# flatkeys_sch.net
KiCad netlist of a schematic drawn in EasyEDA
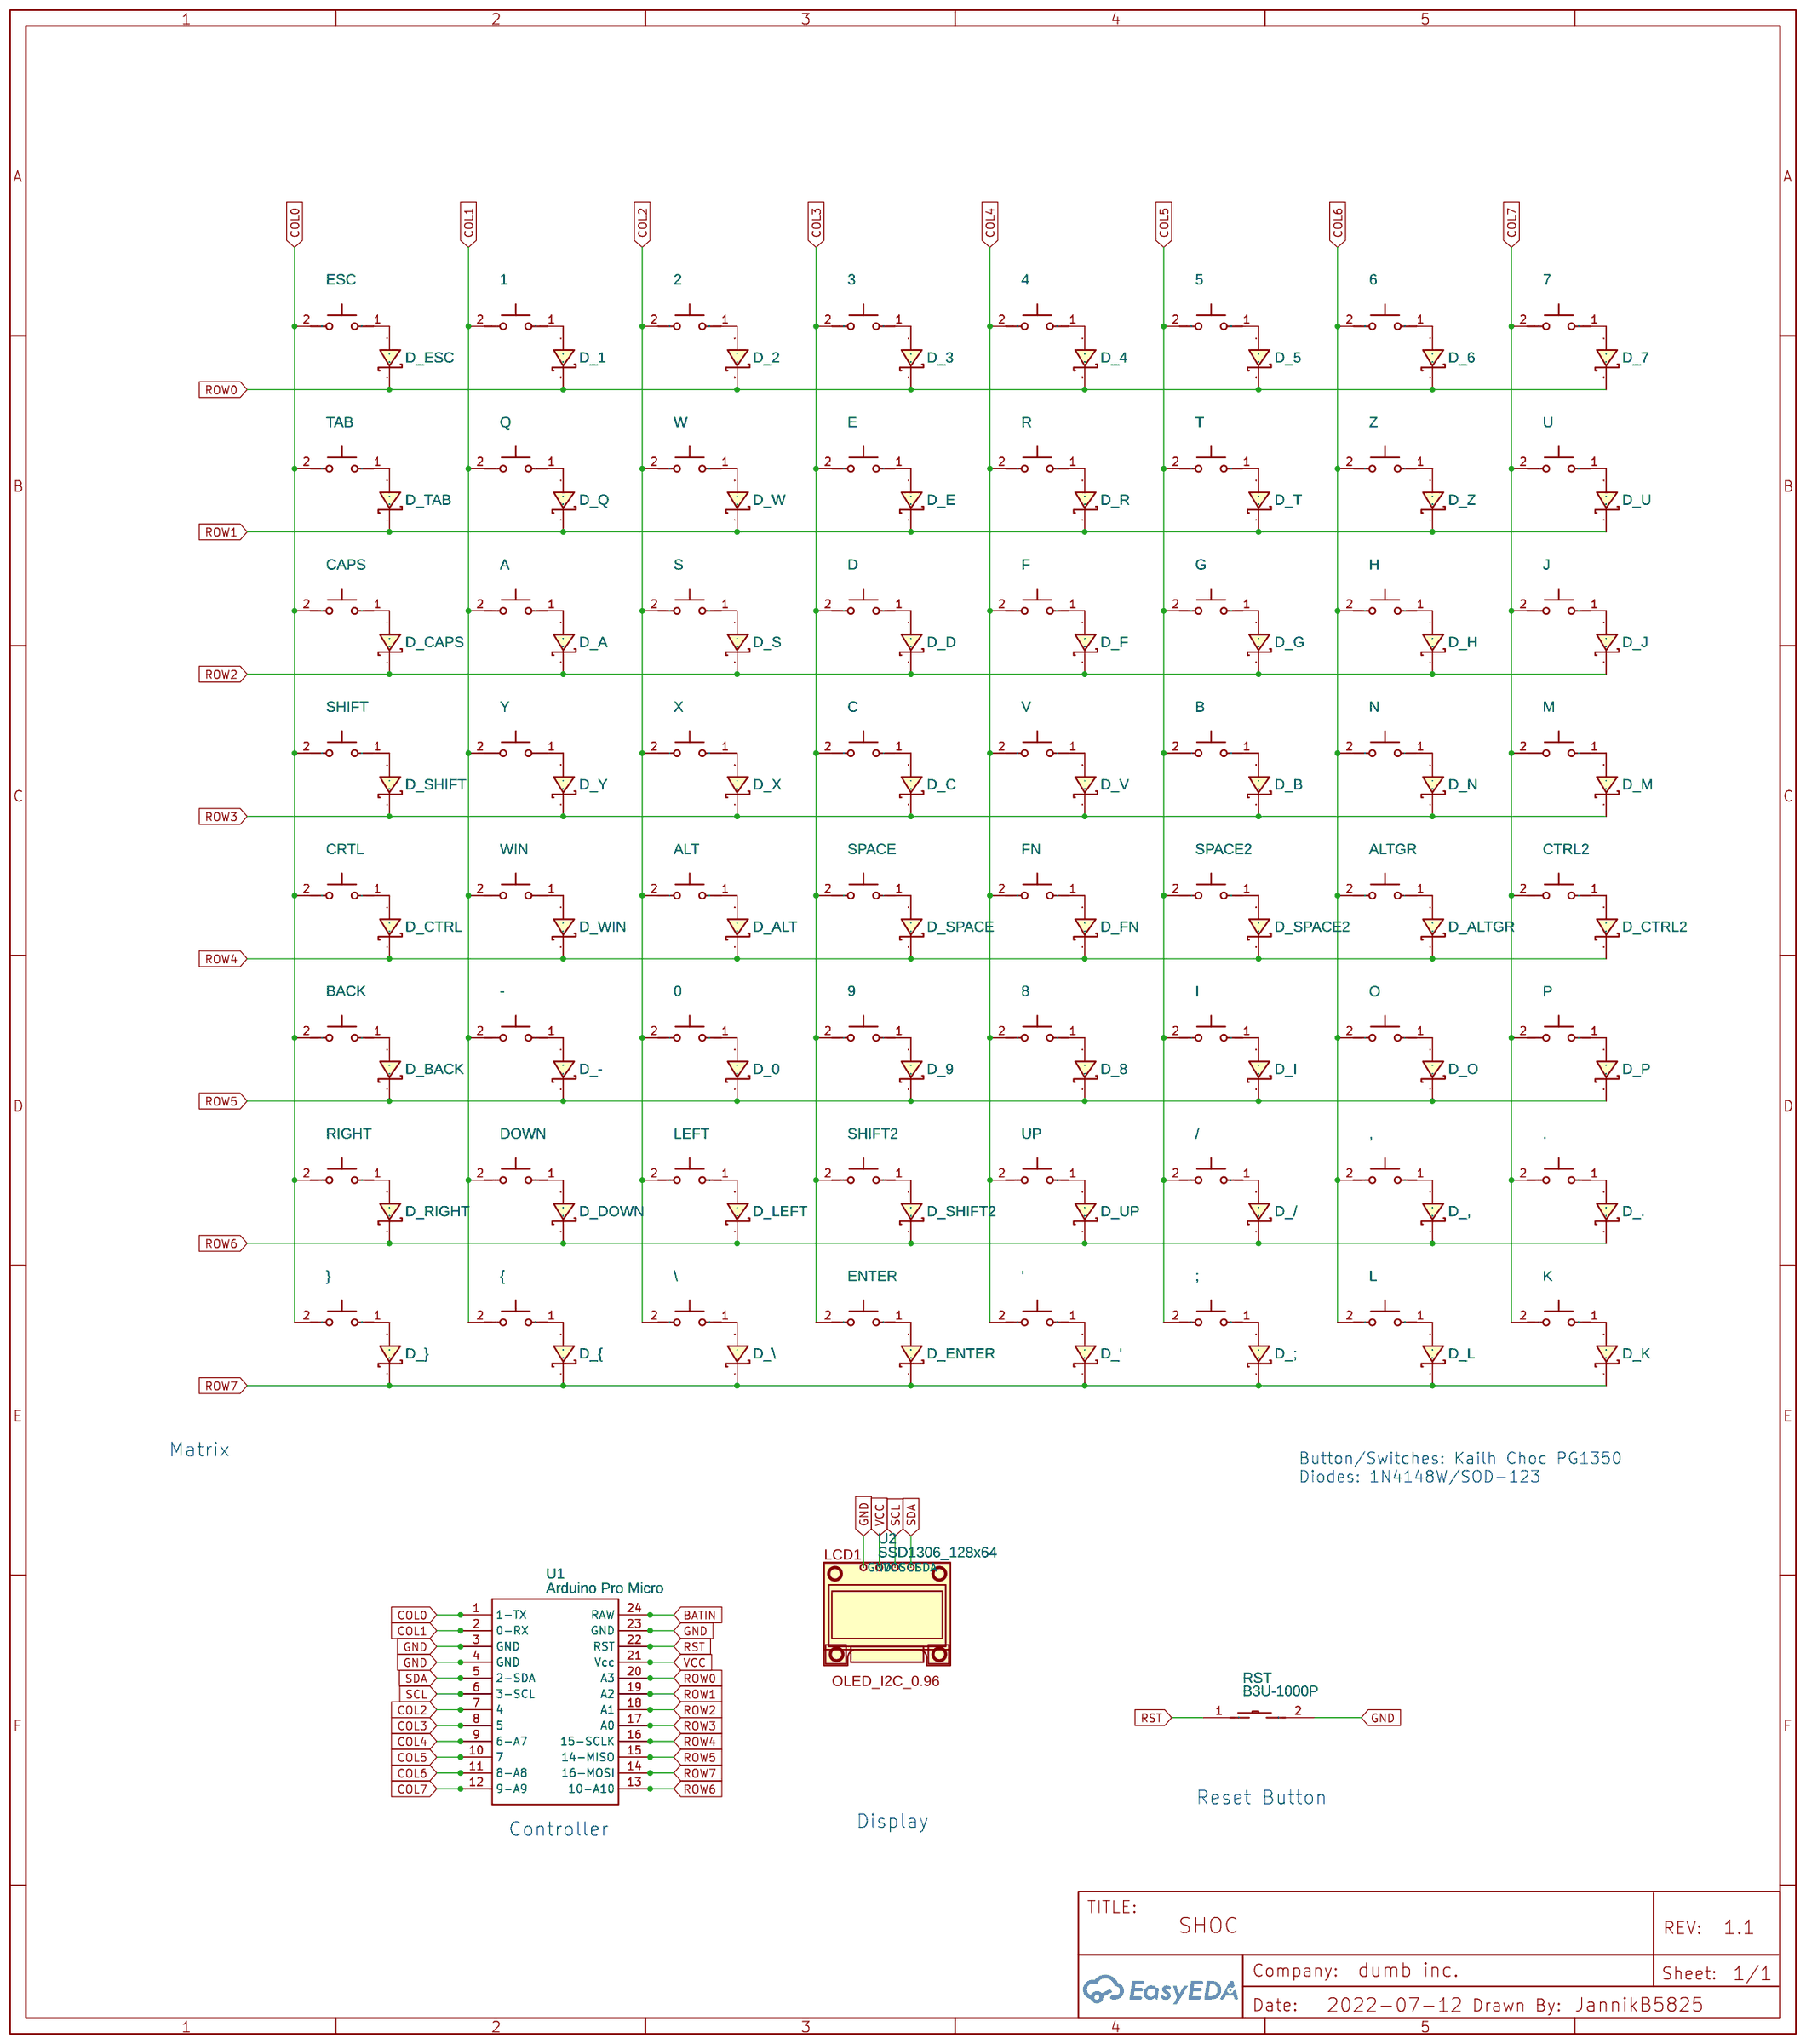
[diagram p0: schematic sheet]

(export (version "E")
  (design (tool "Eeschema 10.0.6"))
  (components
    (comp (ref "'")
      (value "PG1350")
      (fields (field (name "Manufacturer Part") "CPG135001D02") (field (name "Manufacturer") "Kailh"))
      (libsource (lib "") (part "PG1350_43"))
    )
    (comp (ref ",")
      (value "PG1350")
      (fields (field (name "Manufacturer Part") "CPG135001D02") (field (name "Manufacturer") "Kailh"))
      (libsource (lib "") (part "PG1350_28"))
    )
    (comp (ref "-")
      (value "PG1350")
      (fields (field (name "Manufacturer Part") "CPG135001D02") (field (name "Manufacturer") "Kailh"))
      (libsource (lib "") (part "PG1350_25"))
    )
    (comp (ref ".")
      (value "PG1350")
      (fields (field (name "Manufacturer Part") "CPG135001D02") (field (name "Manufacturer") "Kailh"))
      (libsource (lib "") (part "PG1350_46"))
    )
    (comp (ref "/")
      (value "PG1350")
      (fields (field (name "Manufacturer Part") "CPG135001D02") (field (name "Manufacturer") "Kailh"))
      (libsource (lib "") (part "PG1350_21"))
    )
    (comp (ref "0")
      (value "PG1350")
      (fields (field (name "Manufacturer Part") "CPG135001D02") (field (name "Manufacturer") "Kailh"))
      (libsource (lib "") (part "PG1350_2"))
    )
    (comp (ref "1")
      (value "PG1350")
      (fields (field (name "Manufacturer Part") "CPG135001D02") (field (name "Manufacturer") "Kailh"))
      (libsource (lib "") (part "PG1350_2"))
    )
    (comp (ref "2")
      (value "PG1350")
      (fields (field (name "Manufacturer Part") "CPG135001D02") (field (name "Manufacturer") "Kailh"))
      (libsource (lib "") (part "PG1350_2"))
    )
    (comp (ref "3")
      (value "PG1350")
      (fields (field (name "Manufacturer Part") "CPG135001D02") (field (name "Manufacturer") "Kailh"))
      (libsource (lib "") (part "PG1350_2"))
    )
    (comp (ref "4")
      (value "PG1350")
      (fields (field (name "Manufacturer Part") "CPG135001D02") (field (name "Manufacturer") "Kailh"))
      (libsource (lib "") (part "PG1350_2"))
    )
    (comp (ref "5")
      (value "PG1350")
      (fields (field (name "Manufacturer Part") "CPG135001D02") (field (name "Manufacturer") "Kailh"))
      (libsource (lib "") (part "PG1350_2"))
    )
    (comp (ref "6")
      (value "PG1350")
      (fields (field (name "Manufacturer Part") "CPG135001D02") (field (name "Manufacturer") "Kailh"))
      (libsource (lib "") (part "PG1350_2"))
    )
    (comp (ref "7")
      (value "PG1350")
      (fields (field (name "Manufacturer Part") "CPG135001D02") (field (name "Manufacturer") "Kailh"))
      (libsource (lib "") (part "PG1350_2"))
    )
    (comp (ref "8")
      (value "PG1350")
      (fields (field (name "Manufacturer Part") "CPG135001D02") (field (name "Manufacturer") "Kailh"))
      (libsource (lib "") (part "PG1350_2"))
    )
    (comp (ref "9")
      (value "PG1350")
      (fields (field (name "Manufacturer Part") "CPG135001D02") (field (name "Manufacturer") "Kailh"))
      (libsource (lib "") (part "PG1350_2"))
    )
    (comp (ref ";")
      (value "PG1350")
      (fields (field (name "Manufacturer Part") "CPG135001D02") (field (name "Manufacturer") "Kailh"))
      (libsource (lib "") (part "PG1350_11"))
    )
    (comp (ref "A")
      (value "PG1350")
      (fields (field (name "Manufacturer Part") "?"))
      (libsource (lib "") (part "Unknown_205_-1510"))
    )
    (comp (ref "ALT")
      (value "PG1350")
      (fields (field (name "Manufacturer Part") "CPG135001D02") (field (name "Manufacturer") "Kailh"))
      (libsource (lib "") (part "PG1350_6"))
    )
    (comp (ref "ALTGR")
      (value "PG1350")
      (fields (field (name "Manufacturer Part") "CPG135001D02") (field (name "Manufacturer") "Kailh"))
      (libsource (lib "") (part "PG1350_37"))
    )
    (comp (ref "B")
      (value "PG1350")
      (fields (field (name "Manufacturer Part") "CPG135001D02") (field (name "Manufacturer") "Kailh"))
      (libsource (lib "") (part "PG1350_19"))
    )
    (comp (ref "BACK")
      (value "PG1350")
      (fields (field (name "Manufacturer Part") "CPG135001D02") (field (name "Manufacturer") "Kailh"))
      (libsource (lib "") (part "PG1350_3"))
    )
    (comp (ref "C")
      (value "PG1350")
      (fields (field (name "Manufacturer Part") "CPG135001D02") (field (name "Manufacturer") "Kailh"))
      (libsource (lib "") (part "PG1350_31"))
    )
    (comp (ref "CAPS")
      (value "PG1350")
      (fields (field (name "Manufacturer Part") "CPG135001D02") (field (name "Manufacturer") "Kailh"))
      (libsource (lib "") (part "PG1350_52"))
    )
    (comp (ref "CRTL")
      (value "PG1350")
      (fields (field (name "Manufacturer Part") "CPG135001D02") (field (name "Manufacturer") "Kailh"))
      (libsource (lib "") (part "PG1350_12"))
    )
    (comp (ref "CTRL2")
      (value "PG1350")
      (fields (field (name "Manufacturer Part") "CPG135001D02") (field (name "Manufacturer") "Kailh"))
      (libsource (lib "") (part "PG1350_4"))
    )
    (comp (ref "D")
      (value "PG1350")
      (fields (field (name "Manufacturer Part") "CPG135001D02") (field (name "Manufacturer") "Kailh"))
      (libsource (lib "") (part "PG1350_7"))
    )
    (comp (ref "DOWN")
      (value "PG1350")
      (fields (field (name "Manufacturer Part") "CPG135001D02") (field (name "Manufacturer") "Kailh"))
      (libsource (lib "") (part "PG1350"))
    )
    (comp (ref "D_'")
      (value "MBR2H200SFT3G")
      (fields (field (name "Manufacturer") "ON Semiconductor"))
      (libsource (lib "") (part "MBR2H200SFT3G_10"))
    )
    (comp (ref "D_,")
      (value "MBR2H200SFT3G")
      (fields (field (name "Manufacturer") "ON Semiconductor"))
      (libsource (lib "") (part "MBR2H200SFT3G_22"))
    )
    (comp (ref "D_-")
      (value "MBR2H200SFT3G")
      (fields (field (name "Manufacturer") "ON Semiconductor"))
      (libsource (lib "") (part "MBR2H200SFT3G_40"))
    )
    (comp (ref "D_.")
      (value "MBR2H200SFT3G")
      (fields (field (name "Manufacturer") "ON Semiconductor"))
      (libsource (lib "") (part "MBR2H200SFT3G_17"))
    )
    (comp (ref "D_/")
      (value "MBR2H200SFT3G")
      (fields (field (name "Manufacturer") "ON Semiconductor"))
      (libsource (lib "") (part "MBR2H200SFT3G_13"))
    )
    (comp (ref "D_0")
      (value "MBR2H200SFT3G")
      (fields (field (name "Manufacturer") "ON Semiconductor"))
      (libsource (lib "") (part "MBR2H200SFT3G_4"))
    )
    (comp (ref "D_1")
      (value "MBR2H200SFT3G")
      (fields (field (name "Manufacturer") "ON Semiconductor"))
      (libsource (lib "") (part "MBR2H200SFT3G_4"))
    )
    (comp (ref "D_2")
      (value "MBR2H200SFT3G")
      (fields (field (name "Manufacturer") "ON Semiconductor"))
      (libsource (lib "") (part "MBR2H200SFT3G_4"))
    )
    (comp (ref "D_3")
      (value "MBR2H200SFT3G")
      (fields (field (name "Manufacturer") "ON Semiconductor"))
      (libsource (lib "") (part "MBR2H200SFT3G_4"))
    )
    (comp (ref "D_4")
      (value "MBR2H200SFT3G")
      (fields (field (name "Manufacturer") "ON Semiconductor"))
      (libsource (lib "") (part "MBR2H200SFT3G_4"))
    )
    (comp (ref "D_5")
      (value "MBR2H200SFT3G")
      (fields (field (name "Manufacturer") "ON Semiconductor"))
      (libsource (lib "") (part "MBR2H200SFT3G_4"))
    )
    (comp (ref "D_6")
      (value "MBR2H200SFT3G")
      (fields (field (name "Manufacturer") "ON Semiconductor"))
      (libsource (lib "") (part "MBR2H200SFT3G_4"))
    )
    (comp (ref "D_7")
      (value "MBR2H200SFT3G")
      (fields (field (name "Manufacturer") "ON Semiconductor"))
      (libsource (lib "") (part "MBR2H200SFT3G_4"))
    )
    (comp (ref "D_8")
      (value "MBR2H200SFT3G")
      (fields (field (name "Manufacturer") "ON Semiconductor"))
      (libsource (lib "") (part "MBR2H200SFT3G_4"))
    )
    (comp (ref "D_9")
      (value "MBR2H200SFT3G")
      (fields (field (name "Manufacturer") "ON Semiconductor"))
      (libsource (lib "") (part "MBR2H200SFT3G_4"))
    )
    (comp (ref "D_;")
      (value "MBR2H200SFT3G")
      (fields (field (name "Manufacturer") "ON Semiconductor"))
      (libsource (lib "") (part "MBR2H200SFT3G_9"))
    )
    (comp (ref "D_A")
      (value "MBR2H200SFT3G")
      (fields (field (name "Manufacturer") "ON Semiconductor"))
      (libsource (lib "") (part "MBR2H200SFT3G_44"))
    )
    (comp (ref "D_ALT")
      (value "MBR2H200SFT3G")
      (fields (field (name "Manufacturer") "ON Semiconductor"))
      (libsource (lib "") (part "MBR2H200SFT3G_14"))
    )
    (comp (ref "D_ALTGR")
      (value "MBR2H200SFT3G")
      (fields (field (name "Manufacturer") "ON Semiconductor"))
      (libsource (lib "") (part "MBR2H200SFT3G_34"))
    )
    (comp (ref "D_B")
      (value "MBR2H200SFT3G")
      (fields (field (name "Manufacturer") "ON Semiconductor"))
      (libsource (lib "") (part "MBR2H200SFT3G_28"))
    )
    (comp (ref "D_BACK")
      (value "MBR2H200SFT3G")
      (fields (field (name "Manufacturer") "ON Semiconductor"))
      (libsource (lib "") (part "MBR2H200SFT3G_21"))
    )
    (comp (ref "D_C")
      (value "MBR2H200SFT3G")
      (fields (field (name "Manufacturer") "ON Semiconductor"))
      (libsource (lib "") (part "MBR2H200SFT3G_24"))
    )
    (comp (ref "D_CAPS")
      (value "MBR2H200SFT3G")
      (fields (field (name "Manufacturer") "ON Semiconductor"))
      (libsource (lib "") (part "MBR2H200SFT3G_43"))
    )
    (comp (ref "D_CTRL")
      (value "MBR2H200SFT3G")
      (fields (field (name "Manufacturer") "ON Semiconductor"))
      (libsource (lib "") (part "MBR2H200SFT3G"))
    )
    (comp (ref "D_CTRL2")
      (value "MBR2H200SFT3G")
      (fields (field (name "Manufacturer") "ON Semiconductor"))
      (libsource (lib "") (part "MBR2H200SFT3G"))
    )
    (comp (ref "D_D")
      (value "MBR2H200SFT3G")
      (fields (field (name "Manufacturer") "ON Semiconductor"))
      (libsource (lib "") (part "MBR2H200SFT3G_38"))
    )
    (comp (ref "D_DOWN")
      (value "MBR2H200SFT3G")
      (fields (field (name "Manufacturer") "ON Semiconductor"))
      (libsource (lib "") (part "MBR2H200SFT3G_25"))
    )
    (comp (ref "D_E")
      (value "MBR2H200SFT3G")
      (fields (field (name "Manufacturer") "ON Semiconductor"))
      (libsource (lib "") (part "MBR2H200SFT3G_41"))
    )
    (comp (ref "D_ENTER")
      (value "MBR2H200SFT3G")
      (fields (field (name "Manufacturer") "ON Semiconductor"))
      (libsource (lib "") (part "MBR2H200SFT3G_47"))
    )
    (comp (ref "D_ESC")
      (value "MBR2H200SFT3G")
      (fields (field (name "Manufacturer") "ON Semiconductor"))
      (libsource (lib "") (part "MBR2H200SFT3G_15"))
    )
    (comp (ref "D_F")
      (value "MBR2H200SFT3G")
      (fields (field (name "Manufacturer") "ON Semiconductor"))
      (libsource (lib "") (part "MBR2H200SFT3G_48"))
    )
    (comp (ref "D_FN")
      (value "MBR2H200SFT3G")
      (fields (field (name "Manufacturer") "ON Semiconductor"))
      (libsource (lib "") (part "MBR2H200SFT3G_32"))
    )
    (comp (ref "D_G")
      (value "MBR2H200SFT3G")
      (fields (field (name "Manufacturer") "ON Semiconductor"))
      (libsource (lib "") (part "MBR2H200SFT3G_6"))
    )
    (comp (ref "D_H")
      (value "MBR2H200SFT3G")
      (fields (field (name "Manufacturer") "ON Semiconductor"))
      (libsource (lib "") (part "MBR2H200SFT3G_39"))
    )
    (comp (ref "D_I")
      (value "MBR2H200SFT3G")
      (fields (field (name "Manufacturer") "ON Semiconductor"))
      (libsource (lib "") (part "MBR2H200SFT3G_49"))
    )
    (comp (ref "D_J")
      (value "MBR2H200SFT3G")
      (fields (field (name "Manufacturer") "ON Semiconductor"))
      (libsource (lib "") (part "MBR2H200SFT3G_8"))
    )
    (comp (ref "D_K")
      (value "MBR2H200SFT3G")
      (fields (field (name "Manufacturer") "ON Semiconductor"))
      (libsource (lib "") (part "MBR2H200SFT3G_26"))
    )
    (comp (ref "D_L")
      (value "MBR2H200SFT3G")
      (fields (field (name "Manufacturer") "ON Semiconductor"))
      (libsource (lib "") (part "MBR2H200SFT3G_31"))
    )
    (comp (ref "D_LEFT")
      (value "MBR2H200SFT3G")
      (fields (field (name "Manufacturer") "ON Semiconductor"))
      (libsource (lib "") (part "MBR2H200SFT3G_19"))
    )
    (comp (ref "D_M")
      (value "MBR2H200SFT3G")
      (fields (field (name "Manufacturer") "ON Semiconductor"))
      (libsource (lib "") (part "MBR2H200SFT3G_46"))
    )
    (comp (ref "D_N")
      (value "MBR2H200SFT3G")
      (fields (field (name "Manufacturer") "ON Semiconductor"))
      (libsource (lib "") (part "MBR2H200SFT3G_23"))
    )
    (comp (ref "D_O")
      (value "MBR2H200SFT3G")
      (fields (field (name "Manufacturer") "ON Semiconductor"))
      (libsource (lib "") (part "MBR2H200SFT3G_7"))
    )
    (comp (ref "D_P")
      (value "MBR2H200SFT3G")
      (fields (field (name "Manufacturer") "ON Semiconductor"))
      (libsource (lib "") (part "MBR2H200SFT3G_27"))
    )
    (comp (ref "D_Q")
      (value "MBR2H200SFT3G")
      (fields (field (name "Manufacturer") "ON Semiconductor"))
      (libsource (lib "") (part "MBR2H200SFT3G_11"))
    )
    (comp (ref "D_R")
      (value "MBR2H200SFT3G")
      (fields (field (name "Manufacturer") "ON Semiconductor"))
      (libsource (lib "") (part "MBR2H200SFT3G_51"))
    )
    (comp (ref "D_RIGHT")
      (value "MBR2H200SFT3G")
      (fields (field (name "Manufacturer") "ON Semiconductor"))
      (libsource (lib "") (part "MBR2H200SFT3G_29"))
    )
    (comp (ref "D_S")
      (value "MBR2H200SFT3G")
      (fields (field (name "Manufacturer") "ON Semiconductor"))
      (libsource (lib "") (part "MBR2H200SFT3G_30"))
    )
    (comp (ref "D_SHIFT")
      (value "MBR2H200SFT3G")
      (fields (field (name "Manufacturer") "ON Semiconductor"))
      (libsource (lib "") (part "MBR2H200SFT3G_1"))
    )
    (comp (ref "D_SHIFT2")
      (value "MBR2H200SFT3G")
      (fields (field (name "Manufacturer") "ON Semiconductor"))
      (libsource (lib "") (part "MBR2H200SFT3G_1"))
    )
    (comp (ref "D_SPACE")
      (value "MBR2H200SFT3G")
      (fields (field (name "Manufacturer") "ON Semiconductor"))
      (libsource (lib "") (part "MBR2H200SFT3G_12"))
    )
    (comp (ref "D_SPACE2")
      (value "MBR2H200SFT3G")
      (fields (field (name "Manufacturer") "ON Semiconductor"))
      (libsource (lib "") (part "MBR2H200SFT3G_12"))
    )
    (comp (ref "D_T")
      (value "MBR2H200SFT3G")
      (fields (field (name "Manufacturer") "ON Semiconductor"))
      (libsource (lib "") (part "MBR2H200SFT3G_35"))
    )
    (comp (ref "D_TAB")
      (value "MBR2H200SFT3G")
      (fields (field (name "Manufacturer") "ON Semiconductor"))
      (libsource (lib "") (part "MBR2H200SFT3G_20"))
    )
    (comp (ref "D_U")
      (value "MBR2H200SFT3G")
      (fields (field (name "Manufacturer") "ON Semiconductor"))
      (libsource (lib "") (part "MBR2H200SFT3G_33"))
    )
    (comp (ref "D_UP")
      (value "MBR2H200SFT3G")
      (fields (field (name "Manufacturer") "ON Semiconductor"))
      (libsource (lib "") (part "MBR2H200SFT3G_16"))
    )
    (comp (ref "D_V")
      (value "MBR2H200SFT3G")
      (fields (field (name "Manufacturer") "ON Semiconductor"))
      (libsource (lib "") (part "MBR2H200SFT3G_45"))
    )
    (comp (ref "D_W")
      (value "MBR2H200SFT3G")
      (fields (field (name "Manufacturer") "ON Semiconductor"))
      (libsource (lib "") (part "MBR2H200SFT3G_50"))
    )
    (comp (ref "D_WIN")
      (value "MBR2H200SFT3G")
      (fields (field (name "Manufacturer") "ON Semiconductor"))
      (libsource (lib "") (part "MBR2H200SFT3G_3"))
    )
    (comp (ref "D_X")
      (value "MBR2H200SFT3G")
      (fields (field (name "Manufacturer") "ON Semiconductor"))
      (libsource (lib "") (part "MBR2H200SFT3G_5"))
    )
    (comp (ref "D_Y")
      (value "MBR2H200SFT3G")
      (fields (field (name "Manufacturer") "ON Semiconductor"))
      (libsource (lib "") (part "MBR2H200SFT3G_37"))
    )
    (comp (ref "D_Z")
      (value "MBR2H200SFT3G")
      (fields (field (name "Manufacturer") "ON Semiconductor"))
      (libsource (lib "") (part "MBR2H200SFT3G_2"))
    )
    (comp (ref "D_\\")
      (value "MBR2H200SFT3G")
      (fields (field (name "Manufacturer") "ON Semiconductor"))
      (libsource (lib "") (part "MBR2H200SFT3G_42"))
    )
    (comp (ref "D_{")
      (value "MBR2H200SFT3G")
      (fields (field (name "Manufacturer") "ON Semiconductor"))
      (libsource (lib "") (part "MBR2H200SFT3G_36"))
    )
    (comp (ref "D_}")
      (value "MBR2H200SFT3G")
      (fields (field (name "Manufacturer") "ON Semiconductor"))
      (libsource (lib "") (part "MBR2H200SFT3G_18"))
    )
    (comp (ref "E")
      (value "PG1350")
      (fields (field (name "Manufacturer Part") "CPG135001D02") (field (name "Manufacturer") "Kailh"))
      (libsource (lib "") (part "PG1350_23"))
    )
    (comp (ref "ENTER")
      (value "PG1350")
      (fields (field (name "Manufacturer Part") "CPG135001D02") (field (name "Manufacturer") "Kailh"))
      (libsource (lib "") (part "PG1350_9"))
    )
    (comp (ref "ESC")
      (value "PG1350")
      (fields (field (name "Manufacturer Part") "CPG135001D02") (field (name "Manufacturer") "Kailh"))
      (libsource (lib "") (part "PG1350_26"))
    )
    (comp (ref "F")
      (value "PG1350")
      (fields (field (name "Manufacturer Part") "CPG135001D02") (field (name "Manufacturer") "Kailh"))
      (libsource (lib "") (part "PG1350_44"))
    )
    (comp (ref "FN")
      (value "PG1350")
      (fields (field (name "Manufacturer Part") "CPG135001D02") (field (name "Manufacturer") "Kailh"))
      (libsource (lib "") (part "PG1350_49"))
    )
    (comp (ref "G")
      (value "PG1350")
      (fields (field (name "Manufacturer Part") "CPG135001D02") (field (name "Manufacturer") "Kailh"))
      (libsource (lib "") (part "PG1350_45"))
    )
    (comp (ref "H")
      (value "PG1350")
      (fields (field (name "Manufacturer Part") "CPG135001D02") (field (name "Manufacturer") "Kailh"))
      (libsource (lib "") (part "PG1350_1"))
    )
    (comp (ref "I")
      (value "PG1350")
      (fields (field (name "Manufacturer Part") "CPG135001D02") (field (name "Manufacturer") "Kailh"))
      (libsource (lib "") (part "PG1350_47"))
    )
    (comp (ref "J")
      (value "PG1350")
      (fields (field (name "Manufacturer Part") "CPG135001D02") (field (name "Manufacturer") "Kailh"))
      (libsource (lib "") (part "PG1350_41"))
    )
    (comp (ref "K")
      (value "PG1350")
      (fields (field (name "Manufacturer Part") "CPG135001D02") (field (name "Manufacturer") "Kailh"))
      (libsource (lib "") (part "PG1350_32"))
    )
    (comp (ref "L")
      (value "PG1350")
      (fields (field (name "Manufacturer Part") "CPG135001D02") (field (name "Manufacturer") "Kailh"))
      (libsource (lib "") (part "PG1350_16"))
    )
    (comp (ref "LEFT")
      (value "PG1350")
      (fields (field (name "Manufacturer Part") "CPG135001D02") (field (name "Manufacturer") "Kailh"))
      (libsource (lib "") (part "PG1350_22"))
    )
    (comp (ref "M")
      (value "PG1350")
      (fields (field (name "Manufacturer Part") "CPG135001D02") (field (name "Manufacturer") "Kailh"))
      (libsource (lib "") (part "PG1350_30"))
    )
    (comp (ref "N")
      (value "PG1350")
      (fields (field (name "Manufacturer Part") "CPG135001D02") (field (name "Manufacturer") "Kailh"))
      (libsource (lib "") (part "PG1350_14"))
    )
    (comp (ref "O")
      (value "PG1350")
      (fields (field (name "Manufacturer Part") "CPG135001D02") (field (name "Manufacturer") "Kailh"))
      (libsource (lib "") (part "PG1350_17"))
    )
    (comp (ref "P")
      (value "PG1350")
      (fields (field (name "Manufacturer Part") "CPG135001D02") (field (name "Manufacturer") "Kailh"))
      (libsource (lib "") (part "PG1350_8"))
    )
    (comp (ref "Q")
      (value "PG1350")
      (fields (field (name "Manufacturer Part") "CPG135001D02") (field (name "Manufacturer") "Kailh"))
      (libsource (lib "") (part "PG1350_40"))
    )
    (comp (ref "R")
      (value "PG1350")
      (fields (field (name "Manufacturer Part") "CPG135001D02") (field (name "Manufacturer") "Kailh"))
      (libsource (lib "") (part "PG1350_20"))
    )
    (comp (ref "RIGHT")
      (value "PG1350")
      (fields (field (name "Manufacturer Part") "CPG135001D02") (field (name "Manufacturer") "Kailh"))
      (libsource (lib "") (part "PG1350_42"))
    )
    (comp (ref "RST")
      (value "B3U-1000P")
      (fields (field (name "Manufacturer") "Omron Electronics"))
      (libsource (lib "") (part "B3U-1000P"))
    )
    (comp (ref "S")
      (value "PG1350")
      (fields (field (name "Manufacturer Part") "CPG135001D02") (field (name "Manufacturer") "Kailh"))
      (libsource (lib "") (part "PG1350_34"))
    )
    (comp (ref "SHIFT")
      (value "PG1350")
      (fields (field (name "Manufacturer Part") "CPG135001D02") (field (name "Manufacturer") "Kailh"))
      (libsource (lib "") (part "PG1350_13"))
    )
    (comp (ref "SHIFT2")
      (value "PG1350")
      (fields (field (name "Manufacturer Part") "CPG135001D02") (field (name "Manufacturer") "Kailh"))
      (libsource (lib "") (part "PG1350_13"))
    )
    (comp (ref "SPACE")
      (value "PG1350")
      (fields (field (name "Manufacturer Part") "CPG135001D02") (field (name "Manufacturer") "Kailh"))
      (libsource (lib "") (part "PG1350_33"))
    )
    (comp (ref "SPACE2")
      (value "PG1350")
      (fields (field (name "Manufacturer Part") "CPG135001D02") (field (name "Manufacturer") "Kailh"))
      (libsource (lib "") (part "PG1350_33"))
    )
    (comp (ref "T")
      (value "PG1350")
      (fields (field (name "Manufacturer Part") "CPG135001D02") (field (name "Manufacturer") "Kailh"))
      (libsource (lib "") (part "PG1350_5"))
    )
    (comp (ref "TAB")
      (value "PG1350")
      (fields (field (name "Manufacturer Part") "CPG135001D02") (field (name "Manufacturer") "Kailh"))
      (libsource (lib "") (part "PG1350_38"))
    )
    (comp (ref "U")
      (value "PG1350")
      (fields (field (name "Manufacturer Part") "CPG135001D02") (field (name "Manufacturer") "Kailh"))
      (libsource (lib "") (part "PG1350_51"))
    )
    (comp (ref "U1") (value "Arduino Pro Micro") (libsource (lib "") (part "Arduino Pro Micro")))
    (comp (ref "U2") (value "SSD1306_128x64") (libsource (lib "") (part "SSD1306_128x64")))
    (comp (ref "UP")
      (value "PG1350")
      (fields (field (name "Manufacturer Part") "CPG135001D02") (field (name "Manufacturer") "Kailh"))
      (libsource (lib "") (part "PG1350_18"))
    )
    (comp (ref "V")
      (value "PG1350")
      (fields (field (name "Manufacturer Part") "CPG135001D02") (field (name "Manufacturer") "Kailh"))
      (libsource (lib "") (part "PG1350_15"))
    )
    (comp (ref "W")
      (value "PG1350")
      (fields (field (name "Manufacturer Part") "CPG135001D02") (field (name "Manufacturer") "Kailh"))
      (libsource (lib "") (part "PG1350_27"))
    )
    (comp (ref "WIN")
      (value "PG1350")
      (fields (field (name "Manufacturer Part") "CPG135001D02") (field (name "Manufacturer") "Kailh"))
      (libsource (lib "") (part "PG1350_50"))
    )
    (comp (ref "X")
      (value "PG1350")
      (fields (field (name "Manufacturer Part") "CPG135001D02") (field (name "Manufacturer") "Kailh"))
      (libsource (lib "") (part "PG1350_10"))
    )
    (comp (ref "Y")
      (value "PG1350")
      (fields (field (name "Manufacturer Part") "CPG135001D02") (field (name "Manufacturer") "Kailh"))
      (libsource (lib "") (part "PG1350_39"))
    )
    (comp (ref "Z")
      (value "PG1350")
      (fields (field (name "Manufacturer Part") "CPG135001D02") (field (name "Manufacturer") "Kailh"))
      (libsource (lib "") (part "PG1350_48"))
    )
    (comp (ref "\\")
      (value "PG1350")
      (fields (field (name "Manufacturer Part") "CPG135001D02") (field (name "Manufacturer") "Kailh"))
      (libsource (lib "") (part "PG1350_29"))
    )
    (comp (ref "{")
      (value "PG1350")
      (fields (field (name "Manufacturer Part") "CPG135001D02") (field (name "Manufacturer") "Kailh"))
      (libsource (lib "") (part "PG1350_35"))
    )
    (comp (ref "}")
      (value "PG1350")
      (fields (field (name "Manufacturer Part") "CPG135001D02") (field (name "Manufacturer") "Kailh"))
      (libsource (lib "") (part "PG1350_24"))
    )
  )
  (nets
    (net (code "1") (name "BATIN") (class "Default")
      (node (ref "U1") (pin "24") (pinfunction "RAW_24") (pintype "unspecified"))
    )
    (net (code "2") (name "COL0") (class "Default")
      (node (ref "BACK") (pin "2") (pinfunction "1_2") (pintype "unspecified"))
      (node (ref "CAPS") (pin "2") (pinfunction "1_2") (pintype "unspecified"))
      (node (ref "CRTL") (pin "2") (pinfunction "1_2") (pintype "unspecified"))
      (node (ref "ESC") (pin "2") (pinfunction "1_2") (pintype "unspecified"))
      (node (ref "RIGHT") (pin "2") (pinfunction "1_2") (pintype "unspecified"))
      (node (ref "SHIFT") (pin "2") (pinfunction "1_2") (pintype "unspecified"))
      (node (ref "TAB") (pin "2") (pinfunction "1_2") (pintype "unspecified"))
      (node (ref "U1") (pin "1") (pinfunction "1-TX_1") (pintype "unspecified"))
      (node (ref "}") (pin "2") (pinfunction "1_2") (pintype "unspecified"))
    )
    (net (code "3") (name "COL1") (class "Default")
      (node (ref "-") (pin "2") (pinfunction "1_2") (pintype "unspecified"))
      (node (ref "1") (pin "2") (pinfunction "1_2") (pintype "unspecified"))
      (node (ref "A") (pin "2") (pinfunction "1_2") (pintype "unspecified"))
      (node (ref "DOWN") (pin "2") (pinfunction "1_2") (pintype "unspecified"))
      (node (ref "Q") (pin "2") (pinfunction "1_2") (pintype "unspecified"))
      (node (ref "U1") (pin "2") (pinfunction "0-RX_2") (pintype "unspecified"))
      (node (ref "WIN") (pin "2") (pinfunction "1_2") (pintype "unspecified"))
      (node (ref "Y") (pin "2") (pinfunction "1_2") (pintype "unspecified"))
      (node (ref "{") (pin "2") (pinfunction "1_2") (pintype "unspecified"))
    )
    (net (code "4") (name "COL2") (class "Default")
      (node (ref "0") (pin "2") (pinfunction "1_2") (pintype "unspecified"))
      (node (ref "2") (pin "2") (pinfunction "1_2") (pintype "unspecified"))
      (node (ref "ALT") (pin "2") (pinfunction "1_2") (pintype "unspecified"))
      (node (ref "LEFT") (pin "2") (pinfunction "1_2") (pintype "unspecified"))
      (node (ref "S") (pin "2") (pinfunction "1_2") (pintype "unspecified"))
      (node (ref "U1") (pin "7") (pinfunction "4_7") (pintype "unspecified"))
      (node (ref "W") (pin "2") (pinfunction "1_2") (pintype "unspecified"))
      (node (ref "X") (pin "2") (pinfunction "1_2") (pintype "unspecified"))
      (node (ref "\\") (pin "2") (pinfunction "1_2") (pintype "unspecified"))
    )
    (net (code "5") (name "COL3") (class "Default")
      (node (ref "3") (pin "2") (pinfunction "1_2") (pintype "unspecified"))
      (node (ref "9") (pin "2") (pinfunction "1_2") (pintype "unspecified"))
      (node (ref "C") (pin "2") (pinfunction "1_2") (pintype "unspecified"))
      (node (ref "D") (pin "2") (pinfunction "1_2") (pintype "unspecified"))
      (node (ref "E") (pin "2") (pinfunction "1_2") (pintype "unspecified"))
      (node (ref "ENTER") (pin "2") (pinfunction "1_2") (pintype "unspecified"))
      (node (ref "SHIFT2") (pin "2") (pinfunction "1_2") (pintype "unspecified"))
      (node (ref "SPACE") (pin "2") (pinfunction "1_2") (pintype "unspecified"))
      (node (ref "U1") (pin "8") (pinfunction "5_8") (pintype "unspecified"))
    )
    (net (code "6") (name "COL4") (class "Default")
      (node (ref "'") (pin "2") (pinfunction "1_2") (pintype "unspecified"))
      (node (ref "4") (pin "2") (pinfunction "1_2") (pintype "unspecified"))
      (node (ref "8") (pin "2") (pinfunction "1_2") (pintype "unspecified"))
      (node (ref "F") (pin "2") (pinfunction "1_2") (pintype "unspecified"))
      (node (ref "FN") (pin "2") (pinfunction "1_2") (pintype "unspecified"))
      (node (ref "R") (pin "2") (pinfunction "1_2") (pintype "unspecified"))
      (node (ref "U1") (pin "9") (pinfunction "6-A7_9") (pintype "unspecified"))
      (node (ref "UP") (pin "2") (pinfunction "1_2") (pintype "unspecified"))
      (node (ref "V") (pin "2") (pinfunction "1_2") (pintype "unspecified"))
    )
    (net (code "7") (name "COL5") (class "Default")
      (node (ref "/") (pin "2") (pinfunction "1_2") (pintype "unspecified"))
      (node (ref "5") (pin "2") (pinfunction "1_2") (pintype "unspecified"))
      (node (ref ";") (pin "2") (pinfunction "1_2") (pintype "unspecified"))
      (node (ref "B") (pin "2") (pinfunction "1_2") (pintype "unspecified"))
      (node (ref "G") (pin "2") (pinfunction "1_2") (pintype "unspecified"))
      (node (ref "I") (pin "2") (pinfunction "1_2") (pintype "unspecified"))
      (node (ref "SPACE2") (pin "2") (pinfunction "1_2") (pintype "unspecified"))
      (node (ref "T") (pin "2") (pinfunction "1_2") (pintype "unspecified"))
      (node (ref "U1") (pin "10") (pinfunction "7_10") (pintype "unspecified"))
    )
    (net (code "8") (name "COL6") (class "Default")
      (node (ref ",") (pin "2") (pinfunction "1_2") (pintype "unspecified"))
      (node (ref "6") (pin "2") (pinfunction "1_2") (pintype "unspecified"))
      (node (ref "ALTGR") (pin "2") (pinfunction "1_2") (pintype "unspecified"))
      (node (ref "H") (pin "2") (pinfunction "1_2") (pintype "unspecified"))
      (node (ref "L") (pin "2") (pinfunction "1_2") (pintype "unspecified"))
      (node (ref "N") (pin "2") (pinfunction "1_2") (pintype "unspecified"))
      (node (ref "O") (pin "2") (pinfunction "1_2") (pintype "unspecified"))
      (node (ref "U1") (pin "11") (pinfunction "8-A8_11") (pintype "unspecified"))
      (node (ref "Z") (pin "2") (pinfunction "1_2") (pintype "unspecified"))
    )
    (net (code "9") (name "COL7") (class "Default")
      (node (ref ".") (pin "2") (pinfunction "1_2") (pintype "unspecified"))
      (node (ref "7") (pin "2") (pinfunction "1_2") (pintype "unspecified"))
      (node (ref "CTRL2") (pin "2") (pinfunction "1_2") (pintype "unspecified"))
      (node (ref "J") (pin "2") (pinfunction "1_2") (pintype "unspecified"))
      (node (ref "K") (pin "2") (pinfunction "1_2") (pintype "unspecified"))
      (node (ref "M") (pin "2") (pinfunction "1_2") (pintype "unspecified"))
      (node (ref "P") (pin "2") (pinfunction "1_2") (pintype "unspecified"))
      (node (ref "U") (pin "2") (pinfunction "1_2") (pintype "unspecified"))
      (node (ref "U1") (pin "12") (pinfunction "9-A9_12") (pintype "unspecified"))
    )
    (net (code "10") (name "GND") (class "Default")
      (node (ref "RST") (pin "2") (pinfunction "2_2") (pintype "unspecified"))
      (node (ref "U1") (pin "23") (pinfunction "GND_23") (pintype "unspecified"))
      (node (ref "U1") (pin "3") (pinfunction "GND_3") (pintype "unspecified"))
      (node (ref "U1") (pin "4") (pinfunction "GND_4") (pintype "unspecified"))
      (node (ref "U2") (pin "1") (pinfunction "GND_1") (pintype "unspecified"))
    )
    (net (code "11") (name "Net-('-2)") (class "Default")
      (node (ref "'") (pin "1") (pinfunction "2_1") (pintype "unspecified"))
      (node (ref "D_'") (pin "2") (pinfunction "A_2") (pintype "unspecified"))
    )
    (net (code "12") (name "Net-(,-2)") (class "Default")
      (node (ref ",") (pin "1") (pinfunction "2_1") (pintype "unspecified"))
      (node (ref "D_,") (pin "2") (pinfunction "A_2") (pintype "unspecified"))
    )
    (net (code "13") (name "Net-(--2)") (class "Default")
      (node (ref "-") (pin "1") (pinfunction "2_1") (pintype "unspecified"))
      (node (ref "D_-") (pin "2") (pinfunction "A_2") (pintype "unspecified"))
    )
    (net (code "14") (name "Net-(.-2)") (class "Default")
      (node (ref ".") (pin "1") (pinfunction "2_1") (pintype "unspecified"))
      (node (ref "D_.") (pin "2") (pinfunction "A_2") (pintype "unspecified"))
    )
    (net (code "15") (name "Net-(/-2)") (class "Default")
      (node (ref "/") (pin "1") (pinfunction "2_1") (pintype "unspecified"))
      (node (ref "D_/") (pin "2") (pinfunction "A_2") (pintype "unspecified"))
    )
    (net (code "16") (name "Net-(0-2)") (class "Default")
      (node (ref "0") (pin "1") (pinfunction "2_1") (pintype "unspecified"))
      (node (ref "D_0") (pin "2") (pinfunction "A_2") (pintype "unspecified"))
    )
    (net (code "17") (name "Net-(1-2)") (class "Default")
      (node (ref "1") (pin "1") (pinfunction "2_1") (pintype "unspecified"))
      (node (ref "D_1") (pin "2") (pinfunction "A_2") (pintype "unspecified"))
    )
    (net (code "18") (name "Net-(2-2)") (class "Default")
      (node (ref "2") (pin "1") (pinfunction "2_1") (pintype "unspecified"))
      (node (ref "D_2") (pin "2") (pinfunction "A_2") (pintype "unspecified"))
    )
    (net (code "19") (name "Net-(3-2)") (class "Default")
      (node (ref "3") (pin "1") (pinfunction "2_1") (pintype "unspecified"))
      (node (ref "D_3") (pin "2") (pinfunction "A_2") (pintype "unspecified"))
    )
    (net (code "20") (name "Net-(4-2)") (class "Default")
      (node (ref "4") (pin "1") (pinfunction "2_1") (pintype "unspecified"))
      (node (ref "D_4") (pin "2") (pinfunction "A_2") (pintype "unspecified"))
    )
    (net (code "21") (name "Net-(5-2)") (class "Default")
      (node (ref "5") (pin "1") (pinfunction "2_1") (pintype "unspecified"))
      (node (ref "D_5") (pin "2") (pinfunction "A_2") (pintype "unspecified"))
    )
    (net (code "22") (name "Net-(6-2)") (class "Default")
      (node (ref "6") (pin "1") (pinfunction "2_1") (pintype "unspecified"))
      (node (ref "D_6") (pin "2") (pinfunction "A_2") (pintype "unspecified"))
    )
    (net (code "23") (name "Net-(7-2)") (class "Default")
      (node (ref "7") (pin "1") (pinfunction "2_1") (pintype "unspecified"))
      (node (ref "D_7") (pin "2") (pinfunction "A_2") (pintype "unspecified"))
    )
    (net (code "24") (name "Net-(8-2)") (class "Default")
      (node (ref "8") (pin "1") (pinfunction "2_1") (pintype "unspecified"))
      (node (ref "D_8") (pin "2") (pinfunction "A_2") (pintype "unspecified"))
    )
    (net (code "25") (name "Net-(9-2)") (class "Default")
      (node (ref "9") (pin "1") (pinfunction "2_1") (pintype "unspecified"))
      (node (ref "D_9") (pin "2") (pinfunction "A_2") (pintype "unspecified"))
    )
    (net (code "26") (name "Net-(;-2)") (class "Default")
      (node (ref ";") (pin "1") (pinfunction "2_1") (pintype "unspecified"))
      (node (ref "D_;") (pin "2") (pinfunction "A_2") (pintype "unspecified"))
    )
    (net (code "27") (name "Net-(A-2)") (class "Default")
      (node (ref "A") (pin "1") (pinfunction "2_1") (pintype "unspecified"))
      (node (ref "D_A") (pin "2") (pinfunction "A_2") (pintype "unspecified"))
    )
    (net (code "28") (name "Net-(ALT-2)") (class "Default")
      (node (ref "ALT") (pin "1") (pinfunction "2_1") (pintype "unspecified"))
      (node (ref "D_ALT") (pin "2") (pinfunction "A_2") (pintype "unspecified"))
    )
    (net (code "29") (name "Net-(ALTGR-2)") (class "Default")
      (node (ref "ALTGR") (pin "1") (pinfunction "2_1") (pintype "unspecified"))
      (node (ref "D_ALTGR") (pin "2") (pinfunction "A_2") (pintype "unspecified"))
    )
    (net (code "30") (name "Net-(B-2)") (class "Default")
      (node (ref "B") (pin "1") (pinfunction "2_1") (pintype "unspecified"))
      (node (ref "D_B") (pin "2") (pinfunction "A_2") (pintype "unspecified"))
    )
    (net (code "31") (name "Net-(BACK-2)") (class "Default")
      (node (ref "BACK") (pin "1") (pinfunction "2_1") (pintype "unspecified"))
      (node (ref "D_BACK") (pin "2") (pinfunction "A_2") (pintype "unspecified"))
    )
    (net (code "32") (name "Net-(C-2)") (class "Default")
      (node (ref "C") (pin "1") (pinfunction "2_1") (pintype "unspecified"))
      (node (ref "D_C") (pin "2") (pinfunction "A_2") (pintype "unspecified"))
    )
    (net (code "33") (name "Net-(CAPS-2)") (class "Default")
      (node (ref "CAPS") (pin "1") (pinfunction "2_1") (pintype "unspecified"))
      (node (ref "D_CAPS") (pin "2") (pinfunction "A_2") (pintype "unspecified"))
    )
    (net (code "34") (name "Net-(CRTL-2)") (class "Default")
      (node (ref "CRTL") (pin "1") (pinfunction "2_1") (pintype "unspecified"))
      (node (ref "D_CTRL") (pin "2") (pinfunction "A_2") (pintype "unspecified"))
    )
    (net (code "35") (name "Net-(CTRL2-2)") (class "Default")
      (node (ref "CTRL2") (pin "1") (pinfunction "2_1") (pintype "unspecified"))
      (node (ref "D_CTRL2") (pin "2") (pinfunction "A_2") (pintype "unspecified"))
    )
    (net (code "36") (name "Net-(D-2)") (class "Default")
      (node (ref "D") (pin "1") (pinfunction "2_1") (pintype "unspecified"))
      (node (ref "D_D") (pin "2") (pinfunction "A_2") (pintype "unspecified"))
    )
    (net (code "37") (name "Net-(DOWN-2)") (class "Default")
      (node (ref "DOWN") (pin "1") (pinfunction "2_1") (pintype "unspecified"))
      (node (ref "D_DOWN") (pin "2") (pinfunction "A_2") (pintype "unspecified"))
    )
    (net (code "38") (name "Net-(D_E-A)") (class "Default")
      (node (ref "D_E") (pin "2") (pinfunction "A_2") (pintype "unspecified"))
      (node (ref "E") (pin "1") (pinfunction "2_1") (pintype "unspecified"))
    )
    (net (code "39") (name "Net-(D_ENTER-A)") (class "Default")
      (node (ref "D_ENTER") (pin "2") (pinfunction "A_2") (pintype "unspecified"))
      (node (ref "ENTER") (pin "1") (pinfunction "2_1") (pintype "unspecified"))
    )
    (net (code "40") (name "Net-(D_ESC-A)") (class "Default")
      (node (ref "D_ESC") (pin "2") (pinfunction "A_2") (pintype "unspecified"))
      (node (ref "ESC") (pin "1") (pinfunction "2_1") (pintype "unspecified"))
    )
    (net (code "41") (name "Net-(D_F-A)") (class "Default")
      (node (ref "D_F") (pin "2") (pinfunction "A_2") (pintype "unspecified"))
      (node (ref "F") (pin "1") (pinfunction "2_1") (pintype "unspecified"))
    )
    (net (code "42") (name "Net-(D_FN-A)") (class "Default")
      (node (ref "D_FN") (pin "2") (pinfunction "A_2") (pintype "unspecified"))
      (node (ref "FN") (pin "1") (pinfunction "2_1") (pintype "unspecified"))
    )
    (net (code "43") (name "Net-(D_G-A)") (class "Default")
      (node (ref "D_G") (pin "2") (pinfunction "A_2") (pintype "unspecified"))
      (node (ref "G") (pin "1") (pinfunction "2_1") (pintype "unspecified"))
    )
    (net (code "44") (name "Net-(D_H-A)") (class "Default")
      (node (ref "D_H") (pin "2") (pinfunction "A_2") (pintype "unspecified"))
      (node (ref "H") (pin "1") (pinfunction "2_1") (pintype "unspecified"))
    )
    (net (code "45") (name "Net-(D_I-A)") (class "Default")
      (node (ref "D_I") (pin "2") (pinfunction "A_2") (pintype "unspecified"))
      (node (ref "I") (pin "1") (pinfunction "2_1") (pintype "unspecified"))
    )
    (net (code "46") (name "Net-(D_J-A)") (class "Default")
      (node (ref "D_J") (pin "2") (pinfunction "A_2") (pintype "unspecified"))
      (node (ref "J") (pin "1") (pinfunction "2_1") (pintype "unspecified"))
    )
    (net (code "47") (name "Net-(D_K-A)") (class "Default")
      (node (ref "D_K") (pin "2") (pinfunction "A_2") (pintype "unspecified"))
      (node (ref "K") (pin "1") (pinfunction "2_1") (pintype "unspecified"))
    )
    (net (code "48") (name "Net-(D_L-A)") (class "Default")
      (node (ref "D_L") (pin "2") (pinfunction "A_2") (pintype "unspecified"))
      (node (ref "L") (pin "1") (pinfunction "2_1") (pintype "unspecified"))
    )
    (net (code "49") (name "Net-(D_LEFT-A)") (class "Default")
      (node (ref "D_LEFT") (pin "2") (pinfunction "A_2") (pintype "unspecified"))
      (node (ref "LEFT") (pin "1") (pinfunction "2_1") (pintype "unspecified"))
    )
    (net (code "50") (name "Net-(D_M-A)") (class "Default")
      (node (ref "D_M") (pin "2") (pinfunction "A_2") (pintype "unspecified"))
      (node (ref "M") (pin "1") (pinfunction "2_1") (pintype "unspecified"))
    )
    (net (code "51") (name "Net-(D_N-A)") (class "Default")
      (node (ref "D_N") (pin "2") (pinfunction "A_2") (pintype "unspecified"))
      (node (ref "N") (pin "1") (pinfunction "2_1") (pintype "unspecified"))
    )
    (net (code "52") (name "Net-(D_O-A)") (class "Default")
      (node (ref "D_O") (pin "2") (pinfunction "A_2") (pintype "unspecified"))
      (node (ref "O") (pin "1") (pinfunction "2_1") (pintype "unspecified"))
    )
    (net (code "53") (name "Net-(D_P-A)") (class "Default")
      (node (ref "D_P") (pin "2") (pinfunction "A_2") (pintype "unspecified"))
      (node (ref "P") (pin "1") (pinfunction "2_1") (pintype "unspecified"))
    )
    (net (code "54") (name "Net-(D_Q-A)") (class "Default")
      (node (ref "D_Q") (pin "2") (pinfunction "A_2") (pintype "unspecified"))
      (node (ref "Q") (pin "1") (pinfunction "2_1") (pintype "unspecified"))
    )
    (net (code "55") (name "Net-(D_R-A)") (class "Default")
      (node (ref "D_R") (pin "2") (pinfunction "A_2") (pintype "unspecified"))
      (node (ref "R") (pin "1") (pinfunction "2_1") (pintype "unspecified"))
    )
    (net (code "56") (name "Net-(D_RIGHT-A)") (class "Default")
      (node (ref "D_RIGHT") (pin "2") (pinfunction "A_2") (pintype "unspecified"))
      (node (ref "RIGHT") (pin "1") (pinfunction "2_1") (pintype "unspecified"))
    )
    (net (code "57") (name "Net-(D_S-A)") (class "Default")
      (node (ref "D_S") (pin "2") (pinfunction "A_2") (pintype "unspecified"))
      (node (ref "S") (pin "1") (pinfunction "2_1") (pintype "unspecified"))
    )
    (net (code "58") (name "Net-(D_SHIFT-A)") (class "Default")
      (node (ref "D_SHIFT") (pin "2") (pinfunction "A_2") (pintype "unspecified"))
      (node (ref "SHIFT") (pin "1") (pinfunction "2_1") (pintype "unspecified"))
    )
    (net (code "59") (name "Net-(D_SHIFT2-A)") (class "Default")
      (node (ref "D_SHIFT2") (pin "2") (pinfunction "A_2") (pintype "unspecified"))
      (node (ref "SHIFT2") (pin "1") (pinfunction "2_1") (pintype "unspecified"))
    )
    (net (code "60") (name "Net-(D_SPACE-A)") (class "Default")
      (node (ref "D_SPACE") (pin "2") (pinfunction "A_2") (pintype "unspecified"))
      (node (ref "SPACE") (pin "1") (pinfunction "2_1") (pintype "unspecified"))
    )
    (net (code "61") (name "Net-(D_SPACE2-A)") (class "Default")
      (node (ref "D_SPACE2") (pin "2") (pinfunction "A_2") (pintype "unspecified"))
      (node (ref "SPACE2") (pin "1") (pinfunction "2_1") (pintype "unspecified"))
    )
    (net (code "62") (name "Net-(D_T-A)") (class "Default")
      (node (ref "D_T") (pin "2") (pinfunction "A_2") (pintype "unspecified"))
      (node (ref "T") (pin "1") (pinfunction "2_1") (pintype "unspecified"))
    )
    (net (code "63") (name "Net-(D_TAB-A)") (class "Default")
      (node (ref "D_TAB") (pin "2") (pinfunction "A_2") (pintype "unspecified"))
      (node (ref "TAB") (pin "1") (pinfunction "2_1") (pintype "unspecified"))
    )
    (net (code "64") (name "Net-(D_U-A)") (class "Default")
      (node (ref "D_U") (pin "2") (pinfunction "A_2") (pintype "unspecified"))
      (node (ref "U") (pin "1") (pinfunction "2_1") (pintype "unspecified"))
    )
    (net (code "65") (name "Net-(D_UP-A)") (class "Default")
      (node (ref "D_UP") (pin "2") (pinfunction "A_2") (pintype "unspecified"))
      (node (ref "UP") (pin "1") (pinfunction "2_1") (pintype "unspecified"))
    )
    (net (code "66") (name "Net-(D_V-A)") (class "Default")
      (node (ref "D_V") (pin "2") (pinfunction "A_2") (pintype "unspecified"))
      (node (ref "V") (pin "1") (pinfunction "2_1") (pintype "unspecified"))
    )
    (net (code "67") (name "Net-(D_W-A)") (class "Default")
      (node (ref "D_W") (pin "2") (pinfunction "A_2") (pintype "unspecified"))
      (node (ref "W") (pin "1") (pinfunction "2_1") (pintype "unspecified"))
    )
    (net (code "68") (name "Net-(D_WIN-A)") (class "Default")
      (node (ref "D_WIN") (pin "2") (pinfunction "A_2") (pintype "unspecified"))
      (node (ref "WIN") (pin "1") (pinfunction "2_1") (pintype "unspecified"))
    )
    (net (code "69") (name "Net-(D_X-A)") (class "Default")
      (node (ref "D_X") (pin "2") (pinfunction "A_2") (pintype "unspecified"))
      (node (ref "X") (pin "1") (pinfunction "2_1") (pintype "unspecified"))
    )
    (net (code "70") (name "Net-(D_Y-A)") (class "Default")
      (node (ref "D_Y") (pin "2") (pinfunction "A_2") (pintype "unspecified"))
      (node (ref "Y") (pin "1") (pinfunction "2_1") (pintype "unspecified"))
    )
    (net (code "71") (name "Net-(D_Z-A)") (class "Default")
      (node (ref "D_Z") (pin "2") (pinfunction "A_2") (pintype "unspecified"))
      (node (ref "Z") (pin "1") (pinfunction "2_1") (pintype "unspecified"))
    )
    (net (code "72") (name "Net-(D_\\-A)") (class "Default")
      (node (ref "D_\\") (pin "2") (pinfunction "A_2") (pintype "unspecified"))
      (node (ref "\\") (pin "1") (pinfunction "2_1") (pintype "unspecified"))
    )
    (net (code "73") (name "Net-(D_{-A)") (class "Default")
      (node (ref "D_{") (pin "2") (pinfunction "A_2") (pintype "unspecified"))
      (node (ref "{") (pin "1") (pinfunction "2_1") (pintype "unspecified"))
    )
    (net (code "74") (name "Net-(D_}-A)") (class "Default")
      (node (ref "D_}") (pin "2") (pinfunction "A_2") (pintype "unspecified"))
      (node (ref "}") (pin "1") (pinfunction "2_1") (pintype "unspecified"))
    )
    (net (code "75") (name "ROW0") (class "Default")
      (node (ref "D_1") (pin "1") (pinfunction "C_1") (pintype "unspecified"))
      (node (ref "D_2") (pin "1") (pinfunction "C_1") (pintype "unspecified"))
      (node (ref "D_3") (pin "1") (pinfunction "C_1") (pintype "unspecified"))
      (node (ref "D_4") (pin "1") (pinfunction "C_1") (pintype "unspecified"))
      (node (ref "D_5") (pin "1") (pinfunction "C_1") (pintype "unspecified"))
      (node (ref "D_6") (pin "1") (pinfunction "C_1") (pintype "unspecified"))
      (node (ref "D_7") (pin "1") (pinfunction "C_1") (pintype "unspecified"))
      (node (ref "D_ESC") (pin "1") (pinfunction "C_1") (pintype "unspecified"))
      (node (ref "U1") (pin "20") (pinfunction "A3_20") (pintype "unspecified"))
    )
    (net (code "76") (name "ROW1") (class "Default")
      (node (ref "D_E") (pin "1") (pinfunction "C_1") (pintype "unspecified"))
      (node (ref "D_Q") (pin "1") (pinfunction "C_1") (pintype "unspecified"))
      (node (ref "D_R") (pin "1") (pinfunction "C_1") (pintype "unspecified"))
      (node (ref "D_T") (pin "1") (pinfunction "C_1") (pintype "unspecified"))
      (node (ref "D_TAB") (pin "1") (pinfunction "C_1") (pintype "unspecified"))
      (node (ref "D_U") (pin "1") (pinfunction "C_1") (pintype "unspecified"))
      (node (ref "D_W") (pin "1") (pinfunction "C_1") (pintype "unspecified"))
      (node (ref "D_Z") (pin "1") (pinfunction "C_1") (pintype "unspecified"))
      (node (ref "U1") (pin "19") (pinfunction "A2_19") (pintype "unspecified"))
    )
    (net (code "77") (name "ROW2") (class "Default")
      (node (ref "D_A") (pin "1") (pinfunction "C_1") (pintype "unspecified"))
      (node (ref "D_CAPS") (pin "1") (pinfunction "C_1") (pintype "unspecified"))
      (node (ref "D_D") (pin "1") (pinfunction "C_1") (pintype "unspecified"))
      (node (ref "D_F") (pin "1") (pinfunction "C_1") (pintype "unspecified"))
      (node (ref "D_G") (pin "1") (pinfunction "C_1") (pintype "unspecified"))
      (node (ref "D_H") (pin "1") (pinfunction "C_1") (pintype "unspecified"))
      (node (ref "D_J") (pin "1") (pinfunction "C_1") (pintype "unspecified"))
      (node (ref "D_S") (pin "1") (pinfunction "C_1") (pintype "unspecified"))
      (node (ref "U1") (pin "18") (pinfunction "A1_18") (pintype "unspecified"))
    )
    (net (code "78") (name "ROW3") (class "Default")
      (node (ref "D_B") (pin "1") (pinfunction "C_1") (pintype "unspecified"))
      (node (ref "D_C") (pin "1") (pinfunction "C_1") (pintype "unspecified"))
      (node (ref "D_M") (pin "1") (pinfunction "C_1") (pintype "unspecified"))
      (node (ref "D_N") (pin "1") (pinfunction "C_1") (pintype "unspecified"))
      (node (ref "D_SHIFT") (pin "1") (pinfunction "C_1") (pintype "unspecified"))
      (node (ref "D_V") (pin "1") (pinfunction "C_1") (pintype "unspecified"))
      (node (ref "D_X") (pin "1") (pinfunction "C_1") (pintype "unspecified"))
      (node (ref "D_Y") (pin "1") (pinfunction "C_1") (pintype "unspecified"))
      (node (ref "U1") (pin "17") (pinfunction "A0_17") (pintype "unspecified"))
    )
    (net (code "79") (name "ROW4") (class "Default")
      (node (ref "D_ALT") (pin "1") (pinfunction "C_1") (pintype "unspecified"))
      (node (ref "D_ALTGR") (pin "1") (pinfunction "C_1") (pintype "unspecified"))
      (node (ref "D_CTRL") (pin "1") (pinfunction "C_1") (pintype "unspecified"))
      (node (ref "D_CTRL2") (pin "1") (pinfunction "C_1") (pintype "unspecified"))
      (node (ref "D_FN") (pin "1") (pinfunction "C_1") (pintype "unspecified"))
      (node (ref "D_SPACE") (pin "1") (pinfunction "C_1") (pintype "unspecified"))
      (node (ref "D_SPACE2") (pin "1") (pinfunction "C_1") (pintype "unspecified"))
      (node (ref "D_WIN") (pin "1") (pinfunction "C_1") (pintype "unspecified"))
      (node (ref "U1") (pin "16") (pinfunction "15-SCLK_16") (pintype "unspecified"))
    )
    (net (code "80") (name "ROW5") (class "Default")
      (node (ref "D_-") (pin "1") (pinfunction "C_1") (pintype "unspecified"))
      (node (ref "D_0") (pin "1") (pinfunction "C_1") (pintype "unspecified"))
      (node (ref "D_8") (pin "1") (pinfunction "C_1") (pintype "unspecified"))
      (node (ref "D_9") (pin "1") (pinfunction "C_1") (pintype "unspecified"))
      (node (ref "D_BACK") (pin "1") (pinfunction "C_1") (pintype "unspecified"))
      (node (ref "D_I") (pin "1") (pinfunction "C_1") (pintype "unspecified"))
      (node (ref "D_O") (pin "1") (pinfunction "C_1") (pintype "unspecified"))
      (node (ref "D_P") (pin "1") (pinfunction "C_1") (pintype "unspecified"))
      (node (ref "U1") (pin "15") (pinfunction "14-MISO_15") (pintype "unspecified"))
    )
    (net (code "81") (name "ROW6") (class "Default")
      (node (ref "D_,") (pin "1") (pinfunction "C_1") (pintype "unspecified"))
      (node (ref "D_.") (pin "1") (pinfunction "C_1") (pintype "unspecified"))
      (node (ref "D_/") (pin "1") (pinfunction "C_1") (pintype "unspecified"))
      (node (ref "D_DOWN") (pin "1") (pinfunction "C_1") (pintype "unspecified"))
      (node (ref "D_LEFT") (pin "1") (pinfunction "C_1") (pintype "unspecified"))
      (node (ref "D_RIGHT") (pin "1") (pinfunction "C_1") (pintype "unspecified"))
      (node (ref "D_SHIFT2") (pin "1") (pinfunction "C_1") (pintype "unspecified"))
      (node (ref "D_UP") (pin "1") (pinfunction "C_1") (pintype "unspecified"))
      (node (ref "U1") (pin "13") (pinfunction "10-A10_13") (pintype "unspecified"))
    )
    (net (code "82") (name "ROW7") (class "Default")
      (node (ref "D_'") (pin "1") (pinfunction "C_1") (pintype "unspecified"))
      (node (ref "D_;") (pin "1") (pinfunction "C_1") (pintype "unspecified"))
      (node (ref "D_ENTER") (pin "1") (pinfunction "C_1") (pintype "unspecified"))
      (node (ref "D_K") (pin "1") (pinfunction "C_1") (pintype "unspecified"))
      (node (ref "D_L") (pin "1") (pinfunction "C_1") (pintype "unspecified"))
      (node (ref "D_\\") (pin "1") (pinfunction "C_1") (pintype "unspecified"))
      (node (ref "D_{") (pin "1") (pinfunction "C_1") (pintype "unspecified"))
      (node (ref "D_}") (pin "1") (pinfunction "C_1") (pintype "unspecified"))
      (node (ref "U1") (pin "14") (pinfunction "16-MOSI_14") (pintype "unspecified"))
    )
    (net (code "83") (name "RST") (class "Default")
      (node (ref "RST") (pin "1") (pinfunction "1_1") (pintype "unspecified"))
      (node (ref "U1") (pin "22") (pinfunction "RST_22") (pintype "unspecified"))
    )
    (net (code "84") (name "SCL") (class "Default")
      (node (ref "U1") (pin "6") (pinfunction "3-SCL_6") (pintype "unspecified"))
      (node (ref "U2") (pin "3") (pinfunction "SCL_3") (pintype "unspecified"))
    )
    (net (code "85") (name "SDA") (class "Default")
      (node (ref "U1") (pin "5") (pinfunction "2-SDA_5") (pintype "unspecified"))
      (node (ref "U2") (pin "4") (pinfunction "SDA_4") (pintype "unspecified"))
    )
    (net (code "86") (name "VCC") (class "Default")
      (node (ref "U1") (pin "21") (pinfunction "Vcc_21") (pintype "unspecified"))
      (node (ref "U2") (pin "2") (pinfunction "VCC_2") (pintype "unspecified"))
    )
  )
)
